# IOb.net
KiCad netlist of a schematic drawn in Altium Designer
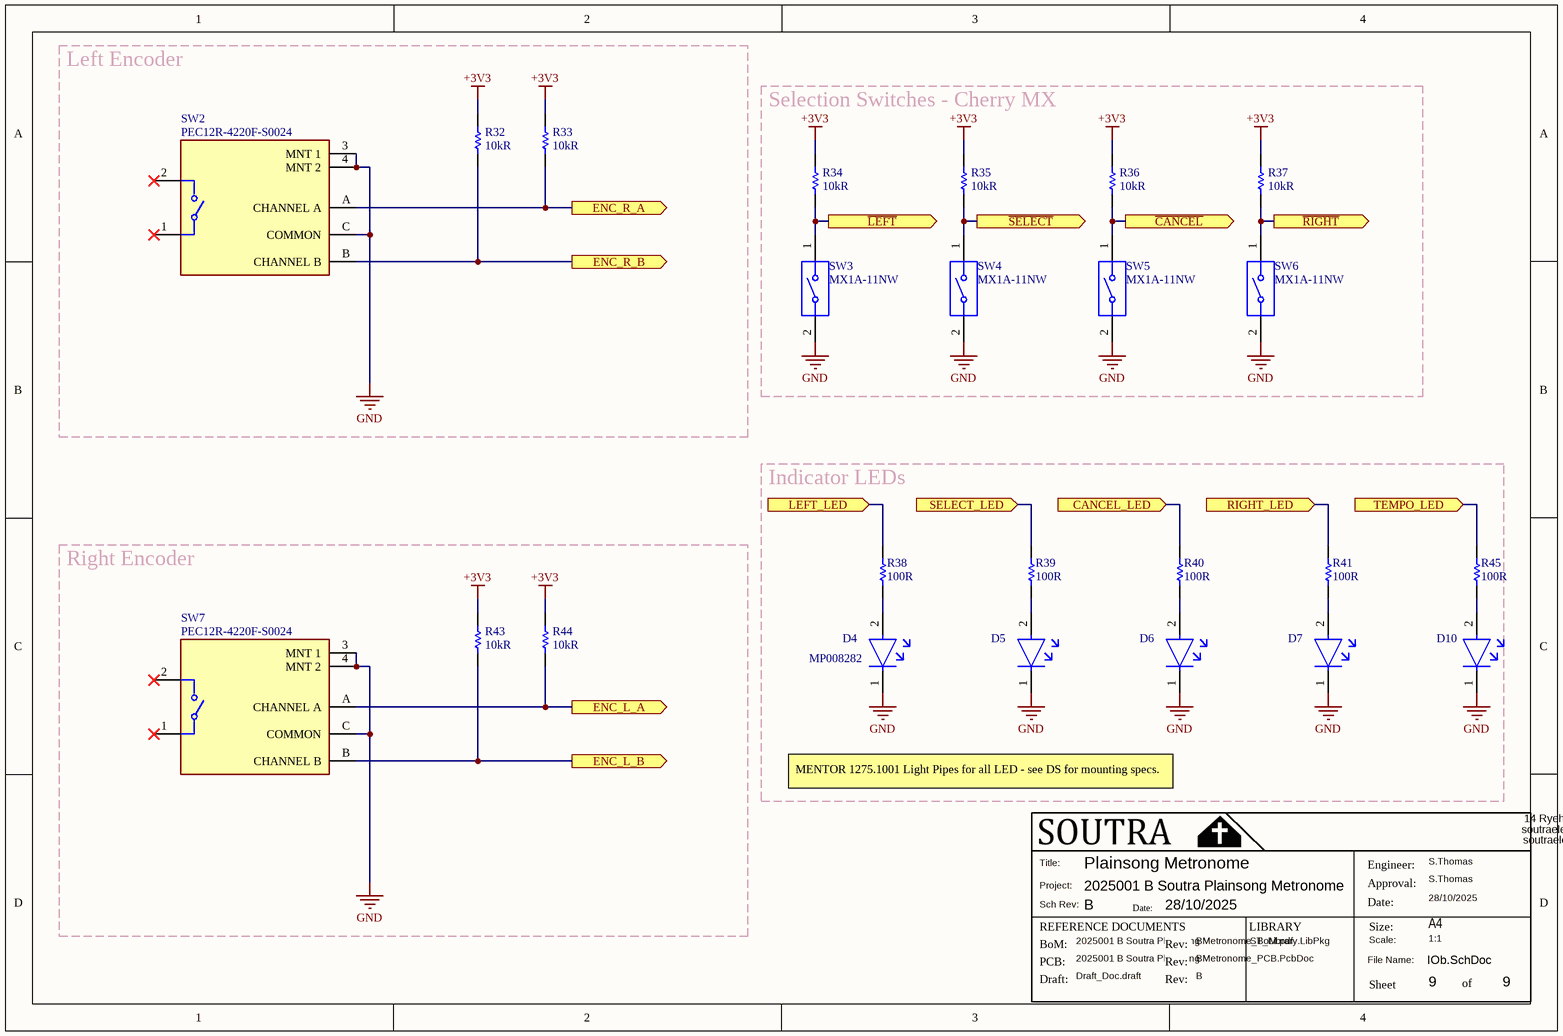
[diagram p0: IOb.SchDoc]

(export (version "E")
  (design (tool "Eeschema 10.0.6"))
  (components
    (comp (ref "D4")
      (value "MP008282")
      (footprint "DIOC_0603_1706X06L")
      (description "Led, Green, 70Mcd, 575Nm, 0603 Rohs Compliant: Yes")
      (fields (field (name "MANUFACTURER") "Multicomp") (field (name "ALTERNATIVE PART") "LG Q396-PS-35"))
      (libsource (lib "ST_Library") (part "MP008282"))
    )
    (comp (ref "D5")
      (value "MP008282")
      (footprint "DIOC_0603_1706X06L")
      (description "Led, Green, 70Mcd, 575Nm, 0603 Rohs Compliant: Yes")
      (fields (field (name "MANUFACTURER") "Multicomp") (field (name "ALTERNATIVE PART") "LG Q396-PS-35"))
      (libsource (lib "ST_Library") (part "MP008282"))
    )
    (comp (ref "D6")
      (value "MP008282")
      (footprint "DIOC_0603_1706X06L")
      (description "Led, Green, 70Mcd, 575Nm, 0603 Rohs Compliant: Yes")
      (fields (field (name "MANUFACTURER") "Multicomp") (field (name "ALTERNATIVE PART") "LG Q396-PS-35"))
      (libsource (lib "ST_Library") (part "MP008282"))
    )
    (comp (ref "D7")
      (value "MP008282")
      (footprint "DIOC_0603_1706X06L")
      (description "Led, Green, 70Mcd, 575Nm, 0603 Rohs Compliant: Yes")
      (fields (field (name "MANUFACTURER") "Multicomp") (field (name "ALTERNATIVE PART") "LG Q396-PS-35"))
      (libsource (lib "ST_Library") (part "MP008282"))
    )
    (comp (ref "D10")
      (value "MP008282")
      (footprint "DIOC_0603_1706X06L")
      (description "Led, Green, 70Mcd, 575Nm, 0603 Rohs Compliant: Yes")
      (fields (field (name "MANUFACTURER") "Multicomp") (field (name "ALTERNATIVE PART") "LG Q396-PS-35"))
      (libsource (lib "ST_Library") (part "MP008282"))
    )
    (comp (ref "R32")
      (value "10kR")
      (footprint "RESC_0805_2013X50X30LL20T20")
      (fields
        (field (name "MANUFACTURER") "Yageo")
        (field (name "MANUFACTURER PART NUMBER") "RC0805JR-0710KL")
        (field (name "TOLERANCE") "5%")
      )
      (libsource (lib "ST_Library") (part "RC0805JR-0710KL"))
    )
    (comp (ref "R33")
      (value "10kR")
      (footprint "RESC_0805_2013X50X30LL20T20")
      (fields
        (field (name "MANUFACTURER") "Yageo")
        (field (name "MANUFACTURER PART NUMBER") "RC0805JR-0710KL")
        (field (name "TOLERANCE") "5%")
      )
      (libsource (lib "ST_Library") (part "RC0805JR-0710KL"))
    )
    (comp (ref "R34")
      (value "10kR")
      (footprint "RESC_0805_2013X50X30LL20T20")
      (fields
        (field (name "MANUFACTURER") "Yageo")
        (field (name "MANUFACTURER PART NUMBER") "RC0805JR-0710KL")
        (field (name "TOLERANCE") "5%")
      )
      (libsource (lib "ST_Library") (part "RC0805JR-0710KL"))
    )
    (comp (ref "R35")
      (value "10kR")
      (footprint "RESC_0805_2013X50X30LL20T20")
      (fields
        (field (name "MANUFACTURER") "Yageo")
        (field (name "MANUFACTURER PART NUMBER") "RC0805JR-0710KL")
        (field (name "TOLERANCE") "5%")
      )
      (libsource (lib "ST_Library") (part "RC0805JR-0710KL"))
    )
    (comp (ref "R36")
      (value "10kR")
      (footprint "RESC_0805_2013X50X30LL20T20")
      (fields
        (field (name "MANUFACTURER") "Yageo")
        (field (name "MANUFACTURER PART NUMBER") "RC0805JR-0710KL")
        (field (name "TOLERANCE") "5%")
      )
      (libsource (lib "ST_Library") (part "RC0805JR-0710KL"))
    )
    (comp (ref "R37")
      (value "10kR")
      (footprint "RESC_0805_2013X50X30LL20T20")
      (fields
        (field (name "MANUFACTURER") "Yageo")
        (field (name "MANUFACTURER PART NUMBER") "RC0805JR-0710KL")
        (field (name "TOLERANCE") "5%")
      )
      (libsource (lib "ST_Library") (part "RC0805JR-0710KL"))
    )
    (comp (ref "R38")
      (value "100R")
      (footprint "RESC_0805_2013X50X30LL20T20")
      (fields
        (field (name "MANUFACTURER") "Vishay Dale")
        (field (name "MANUFACTURER PART NUMBER") "CRCW0805100RFKTA")
        (field (name "TOLERANCE") "1%")
      )
      (libsource (lib "ST_Library") (part "CRCW0805100RFKTA"))
    )
    (comp (ref "R39")
      (value "100R")
      (footprint "RESC_0805_2013X50X30LL20T20")
      (fields
        (field (name "MANUFACTURER") "Vishay Dale")
        (field (name "MANUFACTURER PART NUMBER") "CRCW0805100RFKTA")
        (field (name "TOLERANCE") "1%")
      )
      (libsource (lib "ST_Library") (part "CRCW0805100RFKTA"))
    )
    (comp (ref "R40")
      (value "100R")
      (footprint "RESC_0805_2013X50X30LL20T20")
      (fields
        (field (name "MANUFACTURER") "Vishay Dale")
        (field (name "MANUFACTURER PART NUMBER") "CRCW0805100RFKTA")
        (field (name "TOLERANCE") "1%")
      )
      (libsource (lib "ST_Library") (part "CRCW0805100RFKTA"))
    )
    (comp (ref "R41")
      (value "100R")
      (footprint "RESC_0805_2013X50X30LL20T20")
      (fields
        (field (name "MANUFACTURER") "Vishay Dale")
        (field (name "MANUFACTURER PART NUMBER") "CRCW0805100RFKTA")
        (field (name "TOLERANCE") "1%")
      )
      (libsource (lib "ST_Library") (part "CRCW0805100RFKTA"))
    )
    (comp (ref "R43")
      (value "10kR")
      (footprint "RESC_0805_2013X50X30LL20T20")
      (fields
        (field (name "MANUFACTURER") "Yageo")
        (field (name "MANUFACTURER PART NUMBER") "RC0805JR-0710KL")
        (field (name "TOLERANCE") "5%")
      )
      (libsource (lib "ST_Library") (part "RC0805JR-0710KL"))
    )
    (comp (ref "R44")
      (value "10kR")
      (footprint "RESC_0805_2013X50X30LL20T20")
      (fields
        (field (name "MANUFACTURER") "Yageo")
        (field (name "MANUFACTURER PART NUMBER") "RC0805JR-0710KL")
        (field (name "TOLERANCE") "5%")
      )
      (libsource (lib "ST_Library") (part "RC0805JR-0710KL"))
    )
    (comp (ref "R45")
      (value "100R")
      (footprint "RESC_0805_2013X50X30LL20T20")
      (fields
        (field (name "MANUFACTURER") "Vishay Dale")
        (field (name "MANUFACTURER PART NUMBER") "CRCW0805100RFKTA")
        (field (name "TOLERANCE") "1%")
      )
      (libsource (lib "ST_Library") (part "CRCW0805100RFKTA"))
    )
    (comp (ref "SW2")
      (value "PEC12R-4220F-S0024")
      (footprint "BOURNS_PEC12R-4220F-S0024")
      (description "Rotary Position Encoder, Single, 2 Channels")
      (fields (field (name "MANUFACTURER") "Bourns"))
      (libsource (lib "ST_Library") (part "PEC12R-4220F-S0024"))
    )
    (comp (ref "SW3")
      (value "MX1A-11NW")
      (footprint "CHERRY_MX1A-11NW")
      (fields (field (name "MANUFACTURER") "Cherry"))
      (libsource (lib "ST_Library") (part "MX1A-11NW"))
    )
    (comp (ref "SW4")
      (value "MX1A-11NW")
      (footprint "CHERRY_MX1A-11NW")
      (fields (field (name "MANUFACTURER") "Cherry"))
      (libsource (lib "ST_Library") (part "MX1A-11NW"))
    )
    (comp (ref "SW5")
      (value "MX1A-11NW")
      (footprint "CHERRY_MX1A-11NW")
      (fields (field (name "MANUFACTURER") "Cherry"))
      (libsource (lib "ST_Library") (part "MX1A-11NW"))
    )
    (comp (ref "SW6")
      (value "MX1A-11NW")
      (footprint "CHERRY_MX1A-11NW")
      (fields (field (name "MANUFACTURER") "Cherry"))
      (libsource (lib "ST_Library") (part "MX1A-11NW"))
    )
    (comp (ref "SW7")
      (value "PEC12R-4220F-S0024")
      (footprint "BOURNS_PEC12R-4220F-S0024")
      (description "Rotary Position Encoder, Single, 2 Channels")
      (fields (field (name "MANUFACTURER") "Bourns"))
      (libsource (lib "ST_Library") (part "PEC12R-4220F-S0024"))
    )
  )
  (nets
    (net (code "1") (name "+3V3") (class "Default")
      (node (ref "R32") (pin "2") (pinfunction "2_2") (pintype "passive"))
      (node (ref "R33") (pin "2") (pinfunction "2_2") (pintype "passive"))
      (node (ref "R34") (pin "2") (pinfunction "2_2") (pintype "passive"))
      (node (ref "R35") (pin "2") (pinfunction "2_2") (pintype "passive"))
      (node (ref "R36") (pin "2") (pinfunction "2_2") (pintype "passive"))
      (node (ref "R37") (pin "2") (pinfunction "2_2") (pintype "passive"))
      (node (ref "R43") (pin "2") (pinfunction "2_2") (pintype "passive"))
      (node (ref "R44") (pin "2") (pinfunction "2_2") (pintype "passive"))
    )
    (net (code "2") (name "/CANCEL_LED") (class "Default")
      (node (ref "R40") (pin "1") (pinfunction "1_1") (pintype "passive"))
    )
    (net (code "3") (name "/ENC_L_A") (class "Default")
      (node (ref "R44") (pin "1") (pinfunction "1_1") (pintype "passive"))
      (node (ref "SW7") (pin "A") (pinfunction "CHANNEL_A_A") (pintype "passive"))
    )
    (net (code "4") (name "/ENC_L_B") (class "Default")
      (node (ref "R43") (pin "1") (pinfunction "1_1") (pintype "passive"))
      (node (ref "SW7") (pin "B") (pinfunction "CHANNEL_B_B") (pintype "passive"))
    )
    (net (code "5") (name "/ENC_R_A") (class "Default")
      (node (ref "R33") (pin "1") (pinfunction "1_1") (pintype "passive"))
      (node (ref "SW2") (pin "A") (pinfunction "CHANNEL_A_A") (pintype "passive"))
    )
    (net (code "6") (name "/ENC_R_B") (class "Default")
      (node (ref "R32") (pin "1") (pinfunction "1_1") (pintype "passive"))
      (node (ref "SW2") (pin "B") (pinfunction "CHANNEL_B_B") (pintype "passive"))
    )
    (net (code "7") (name "/LEFT_LED") (class "Default")
      (node (ref "R38") (pin "1") (pinfunction "1_1") (pintype "passive"))
    )
    (net (code "8") (name "/RIGHT_LED") (class "Default")
      (node (ref "R41") (pin "1") (pinfunction "1_1") (pintype "passive"))
    )
    (net (code "9") (name "/SELECT_LED") (class "Default")
      (node (ref "R39") (pin "1") (pinfunction "1_1") (pintype "passive"))
    )
    (net (code "10") (name "/TEMPO_LED") (class "Default")
      (node (ref "R45") (pin "1") (pinfunction "1_1") (pintype "passive"))
    )
    (net (code "11") (name "/~{CANCEL}") (class "Default")
      (node (ref "R36") (pin "1") (pinfunction "1_1") (pintype "passive"))
      (node (ref "SW5") (pin "1") (pinfunction "1_1") (pintype "passive"))
    )
    (net (code "12") (name "/~{LEFT}") (class "Default")
      (node (ref "R34") (pin "1") (pinfunction "1_1") (pintype "passive"))
      (node (ref "SW3") (pin "1") (pinfunction "1_1") (pintype "passive"))
    )
    (net (code "13") (name "/~{RIGHT}") (class "Default")
      (node (ref "R37") (pin "1") (pinfunction "1_1") (pintype "passive"))
      (node (ref "SW6") (pin "1") (pinfunction "1_1") (pintype "passive"))
    )
    (net (code "14") (name "/~{SELECT}") (class "Default")
      (node (ref "R35") (pin "1") (pinfunction "1_1") (pintype "passive"))
      (node (ref "SW4") (pin "1") (pinfunction "1_1") (pintype "passive"))
    )
    (net (code "15") (name "GND") (class "Default")
      (node (ref "D10") (pin "1") (pinfunction "C_1") (pintype "passive"))
      (node (ref "D4") (pin "1") (pinfunction "C_1") (pintype "passive"))
      (node (ref "D5") (pin "1") (pinfunction "C_1") (pintype "passive"))
      (node (ref "D6") (pin "1") (pinfunction "C_1") (pintype "passive"))
      (node (ref "D7") (pin "1") (pinfunction "C_1") (pintype "passive"))
      (node (ref "SW2") (pin "3") (pinfunction "MNT_1_3") (pintype "passive"))
      (node (ref "SW2") (pin "4") (pinfunction "MNT_2_4") (pintype "passive"))
      (node (ref "SW2") (pin "C") (pinfunction "COMMON_C") (pintype "passive"))
      (node (ref "SW3") (pin "2") (pinfunction "2_2") (pintype "passive"))
      (node (ref "SW4") (pin "2") (pinfunction "2_2") (pintype "passive"))
      (node (ref "SW5") (pin "2") (pinfunction "2_2") (pintype "passive"))
      (node (ref "SW6") (pin "2") (pinfunction "2_2") (pintype "passive"))
      (node (ref "SW7") (pin "3") (pinfunction "MNT_1_3") (pintype "passive"))
      (node (ref "SW7") (pin "4") (pinfunction "MNT_2_4") (pintype "passive"))
      (node (ref "SW7") (pin "C") (pinfunction "COMMON_C") (pintype "passive"))
    )
    (net (code "16") (name "Net-(D4-A)") (class "Default")
      (node (ref "D4") (pin "2") (pinfunction "A_2") (pintype "passive"))
      (node (ref "R38") (pin "2") (pinfunction "2_2") (pintype "passive"))
    )
    (net (code "17") (name "Net-(D5-A)") (class "Default")
      (node (ref "D5") (pin "2") (pinfunction "A_2") (pintype "passive"))
      (node (ref "R39") (pin "2") (pinfunction "2_2") (pintype "passive"))
    )
    (net (code "18") (name "Net-(D6-A)") (class "Default")
      (node (ref "D6") (pin "2") (pinfunction "A_2") (pintype "passive"))
      (node (ref "R40") (pin "2") (pinfunction "2_2") (pintype "passive"))
    )
    (net (code "19") (name "Net-(D7-A)") (class "Default")
      (node (ref "D7") (pin "2") (pinfunction "A_2") (pintype "passive"))
      (node (ref "R41") (pin "2") (pinfunction "2_2") (pintype "passive"))
    )
    (net (code "20") (name "Net-(D10-A)") (class "Default")
      (node (ref "D10") (pin "2") (pinfunction "A_2") (pintype "passive"))
      (node (ref "R45") (pin "2") (pinfunction "2_2") (pintype "passive"))
    )
    (net (code "21") (name "unconnected-(SW2-Pad1)") (class "Default")
      (node (ref "SW2") (pin "1") (pinfunction "1_1") (pintype "passive+no_connect"))
    )
    (net (code "22") (name "unconnected-(SW2-Pad2)") (class "Default")
      (node (ref "SW2") (pin "2") (pinfunction "2_2") (pintype "passive+no_connect"))
    )
    (net (code "23") (name "unconnected-(SW7-Pad1)") (class "Default")
      (node (ref "SW7") (pin "1") (pinfunction "1_1") (pintype "passive+no_connect"))
    )
    (net (code "24") (name "unconnected-(SW7-Pad2)") (class "Default")
      (node (ref "SW7") (pin "2") (pinfunction "2_2") (pintype "passive+no_connect"))
    )
  )
)
